# DM3370_IMU_BMI270.net
KiCad netlist of a schematic drawn in Altium Designer
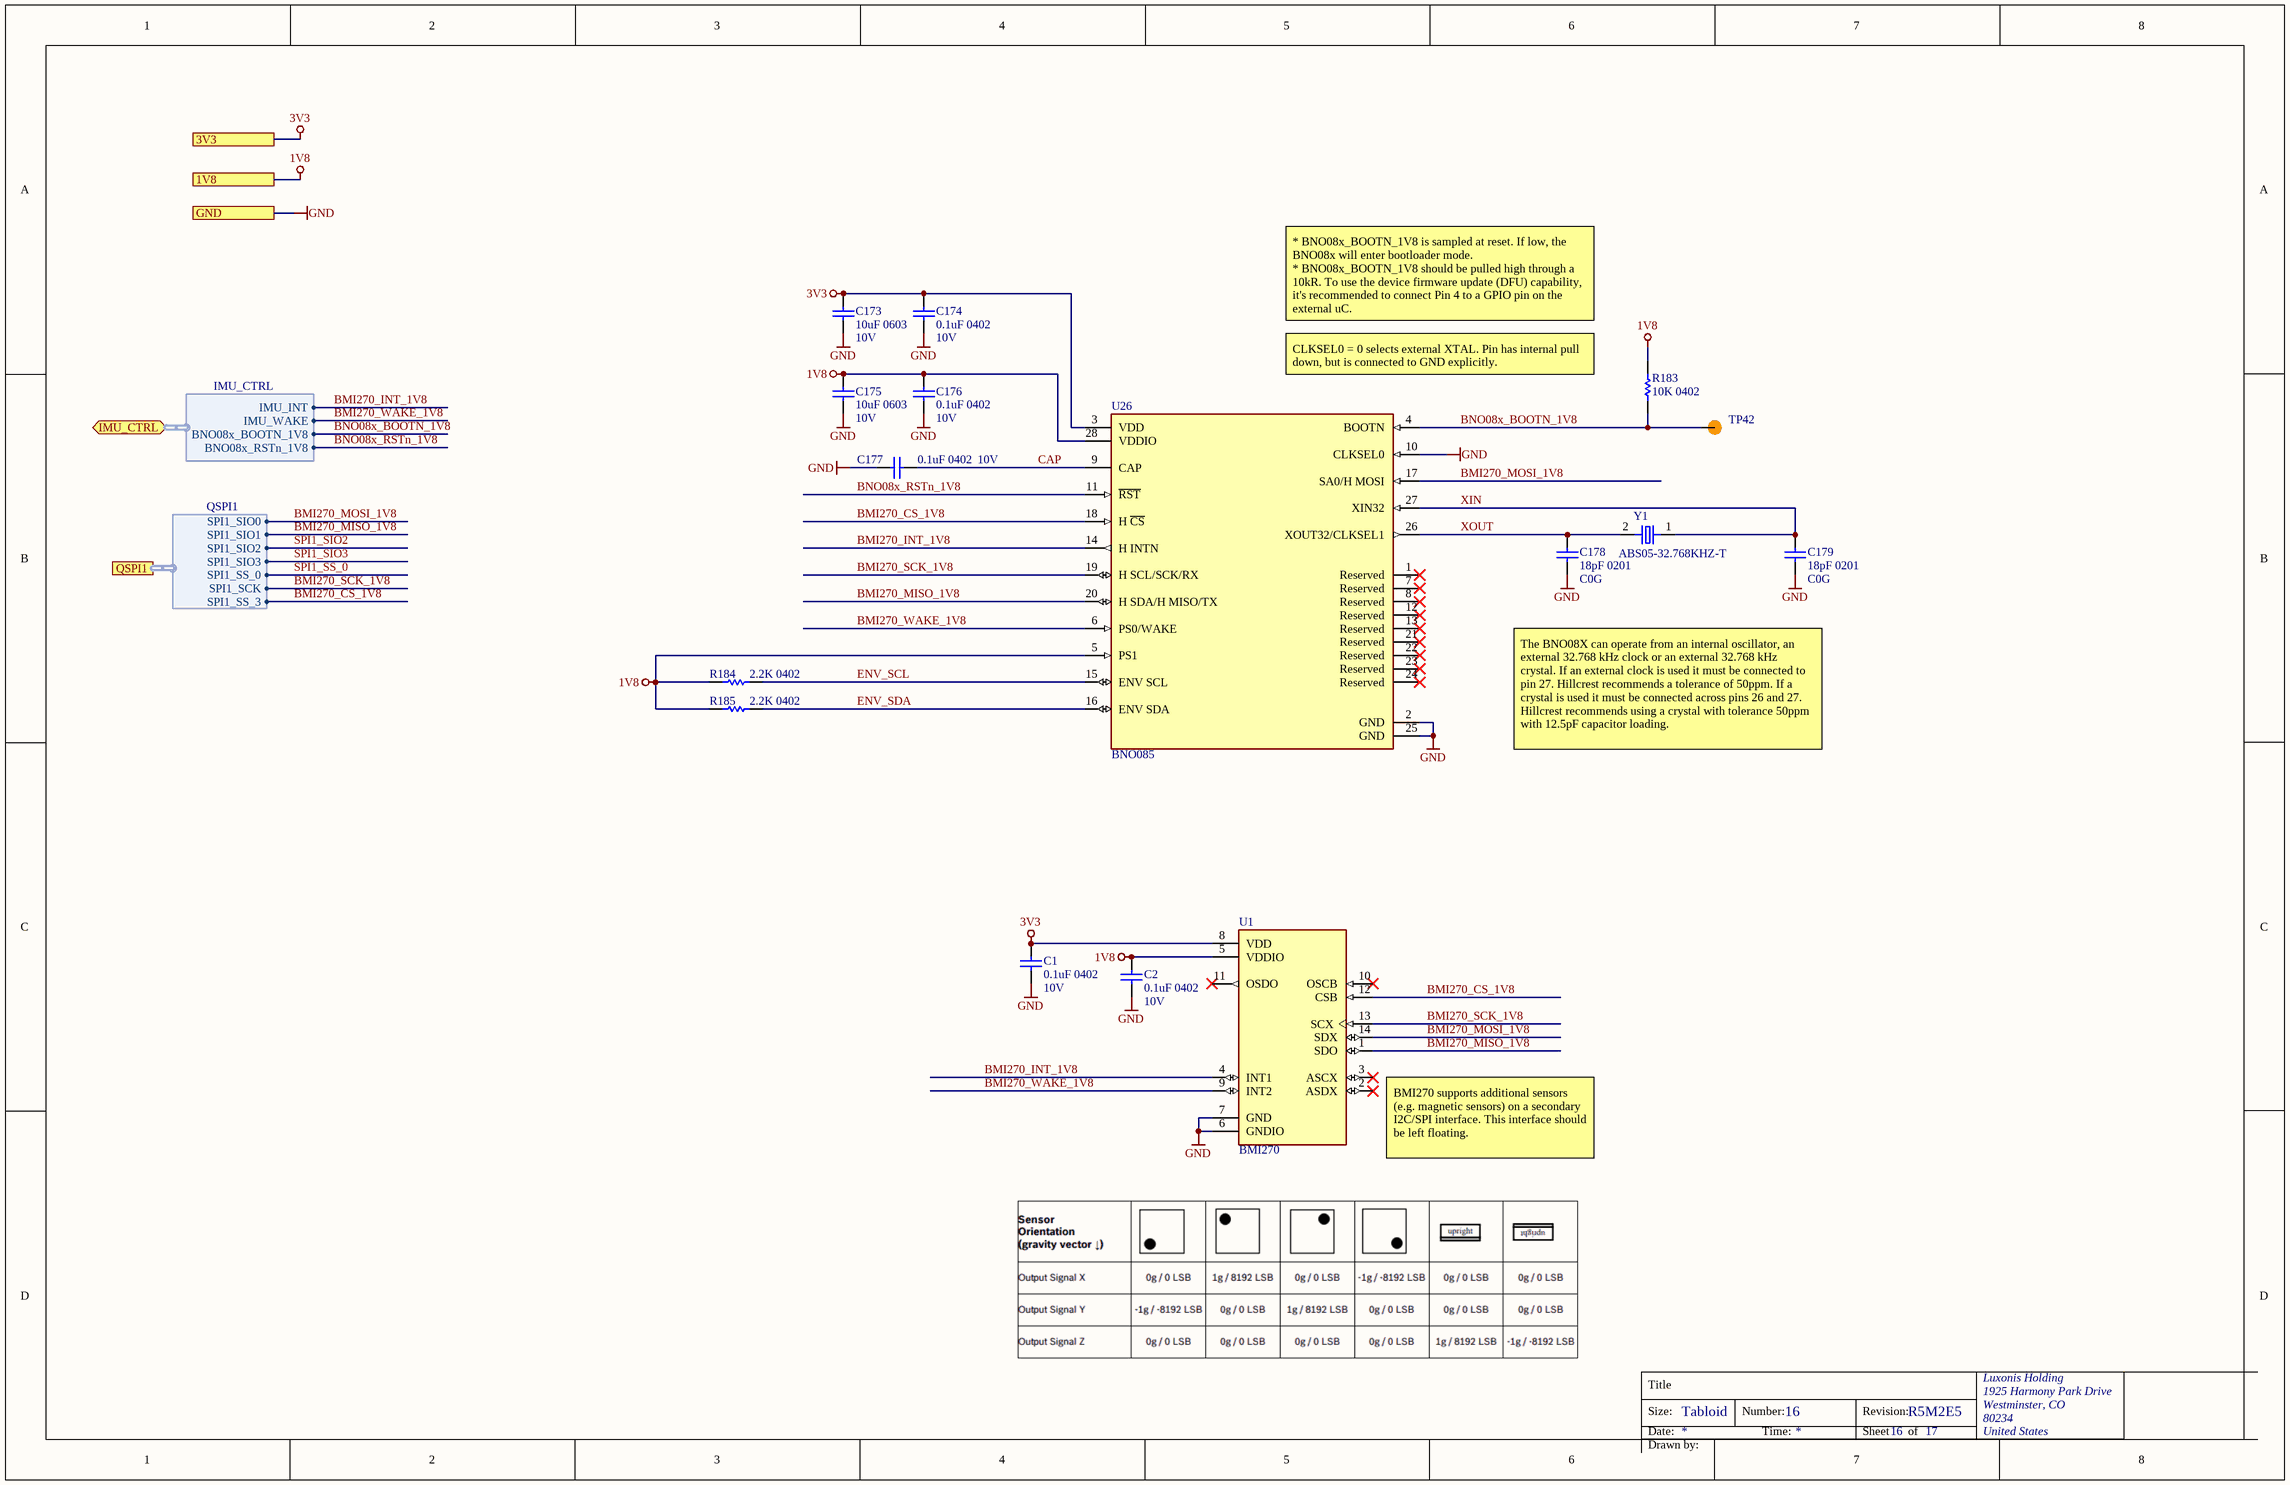
[diagram p0: DM3370_IMU_BMI270.SchDoc]

(export (version "E")
  (design (tool "Eeschema 10.0.6"))
  (components
    (comp (ref "C1")
      (value "0.1uF 0402")
      (footprint "CAP_Altium_Vault_Generic:CAPC0402(1005)70_L")
      (description "CAP CER 0.1UF 10V X7R 0402 5%")
      (fields (field (name "TOLERANCE") "5%") (field (name "VOLTAGE RATING") "10V"))
      (libsource (lib "LuxonisMaster") (part "GRM155R71A104JA01D"))
    )
    (comp (ref "C2")
      (value "0.1uF 0402")
      (footprint "CAP_Altium_Vault_Generic:CAPC0402(1005)70_L")
      (description "CAP CER 0.1UF 10V X7R 0402 5%")
      (fields (field (name "TOLERANCE") "5%") (field (name "VOLTAGE RATING") "10V"))
      (libsource (lib "LuxonisMaster") (part "GRM155R71A104JA01D"))
    )
    (comp (ref "C173")
      (value "10uF 0603")
      (footprint "CAP_Altium_Vault_Generic:CAPC0603(1608)100_L")
      (description "CAP CER 10UF 10V X5R 0603 20%")
      (fields (field (name "TOLERANCE") "20%") (field (name "VOLTAGE RATING") "10V"))
      (libsource (lib "LuxonisMaster") (part "GRM188R61A106ME69D"))
    )
    (comp (ref "C174")
      (value "0.1uF 0402")
      (footprint "CAP_Altium_Vault_Generic:CAPC0402(1005)70_L")
      (description "CAP CER 0.1UF 10V X7R 0402 5%")
      (fields (field (name "TOLERANCE") "5%") (field (name "VOLTAGE RATING") "10V"))
      (libsource (lib "LuxonisMaster") (part "GRM155R71A104JA01D"))
    )
    (comp (ref "C175")
      (value "10uF 0603")
      (footprint "CAP_Altium_Vault_Generic:CAPC0603(1608)100_L")
      (description "CAP CER 10UF 10V X5R 0603 20%")
      (fields (field (name "TOLERANCE") "20%") (field (name "VOLTAGE RATING") "10V"))
      (libsource (lib "LuxonisMaster") (part "GRM188R61A106ME69D"))
    )
    (comp (ref "C176")
      (value "0.1uF 0402")
      (footprint "CAP_Altium_Vault_Generic:CAPC0402(1005)70_L")
      (description "CAP CER 0.1UF 10V X7R 0402 5%")
      (fields (field (name "TOLERANCE") "5%") (field (name "VOLTAGE RATING") "10V"))
      (libsource (lib "LuxonisMaster") (part "GRM155R71A104JA01D"))
    )
    (comp (ref "C177")
      (value "0.1uF 0402")
      (footprint "CAP_Altium_Vault_Generic:CAPC0402(1005)70_L")
      (description "CAP CER 0.1UF 10V X7R 0402 5%")
      (fields (field (name "TOLERANCE") "5%") (field (name "VOLTAGE RATING") "10V"))
      (libsource (lib "LuxonisMaster") (part "GRM155R71A104JA01D"))
    )
    (comp (ref "C178")
      (value "18pF 0201")
      (footprint "CAPC0201(0603)33_L")
      (description "Cap Ceramic 18pF 25V C0G 1% Pad SMD 0201 125C T/R")
      (fields (field (name "TOLERANCE") "1%") (field (name "DIELECTRIC") "C0G"))
      (libsource (lib "LuxonisMaster") (part "GRM0335C1E180FA01D"))
    )
    (comp (ref "C179")
      (value "18pF 0201")
      (footprint "CAPC0201(0603)33_L")
      (description "Cap Ceramic 18pF 25V C0G 1% Pad SMD 0201 125C T/R")
      (fields (field (name "TOLERANCE") "1%") (field (name "DIELECTRIC") "C0G"))
      (libsource (lib "LuxonisMaster") (part "GRM0335C1E180FA01D"))
    )
    (comp (ref "R183")
      (value "10K 0402")
      (footprint "RES_Altium_Vault_Generic:RESC0402(1005)_L")
      (fields (field (name "TOLERANCE") "1%"))
      (libsource (lib "LuxonisMaster") (part "RC0402FR-1310KL"))
    )
    (comp (ref "R184")
      (value "2.2K 0402")
      (footprint "RES_Altium_Vault_Generic:RESC0402(1005)_L")
      (description "RES SMD 2.2K OHM 1% 1/16W 0402")
      (fields (field (name "TOLERANCE") "1%"))
      (libsource (lib "LuxonisMaster") (part "RC0402FR-072K2L"))
    )
    (comp (ref "R185")
      (value "2.2K 0402")
      (footprint "RES_Altium_Vault_Generic:RESC0402(1005)_L")
      (description "RES SMD 2.2K OHM 1% 1/16W 0402")
      (fields (field (name "TOLERANCE") "1%"))
      (libsource (lib "LuxonisMaster") (part "RC0402FR-072K2L"))
    )
    (comp (ref "TP42")
      (value "TP100_200_NS")
      (footprint "LuxonisMaster:TP100_200_NS")
      (libsource (lib "LuxonisMaster") (part "TEST_POINT"))
    )
    (comp (ref "U1")
      (value "BMI270")
      (footprint "XDCR_BMI270")
      (description "Accelerometer, Gyroscope, 6 Axis Sensor IÂ²C, SPI Output")
      (libsource (lib "LuxonisMaster") (part "BMI270"))
    )
    (comp (ref "U26")
      (value "BNO085")
      (footprint "BNO085")
      (description "IMU ACCEL/GYRO/MAG I2C 32BIT")
      (libsource (lib "LuxonisMaster") (part "BNO085"))
    )
    (comp (ref "Y1")
      (value "CMP-096-000000-2")
      (footprint "FP-ABS05-MFG")
      (description "CRYSTAL 32.7680KHZ 12.5PF SMD")
      (fields
        (field (name "TOLERANCE") "20ppm")
        (field (name "MANUFACTURER PART NUMBER 1") "ABS05-32.768KHZ-T")
      )
      (libsource (lib "Luxonis LLC") (part "ABS05-32.768KHZ-T"))
    )
  )
  (nets
    (net (code "3") (name "/BMI270_CS_1V8") (class "Default")
      (node (ref "U1") (pin "12") (pinfunction "CSB_12") (pintype "input"))
      (node (ref "U26") (pin "18") (pinfunction "H_~{CS}_18") (pintype "input"))
    )
    (net (code "4") (name "/BMI270_INT_1V8") (class "Default")
      (node (ref "U1") (pin "4") (pinfunction "INT1_4") (pintype "bidirectional"))
      (node (ref "U26") (pin "14") (pinfunction "H_INTN_14") (pintype "output"))
    )
    (net (code "5") (name "/BMI270_MISO_1V8") (class "Default")
      (node (ref "U1") (pin "1") (pinfunction "SDO_1") (pintype "bidirectional"))
      (node (ref "U26") (pin "20") (pinfunction "H_SDA/H_MISO/TX_20") (pintype "bidirectional"))
    )
    (net (code "6") (name "/BMI270_MOSI_1V8") (class "Default")
      (node (ref "U1") (pin "14") (pinfunction "SDX_14") (pintype "bidirectional"))
      (node (ref "U26") (pin "17") (pinfunction "SA0/H_MOSI_17") (pintype "input"))
    )
    (net (code "7") (name "/BMI270_SCK_1V8") (class "Default")
      (node (ref "U1") (pin "13") (pinfunction "SCX_13") (pintype "input"))
      (node (ref "U26") (pin "19") (pinfunction "H_SCL/SCK/RX_19") (pintype "bidirectional"))
    )
    (net (code "8") (name "/BMI270_WAKE_1V8") (class "Default")
      (node (ref "U1") (pin "9") (pinfunction "INT2_9") (pintype "bidirectional"))
      (node (ref "U26") (pin "6") (pinfunction "PS0/WAKE_6") (pintype "input"))
    )
    (net (code "9") (name "/BNO08x_BOOTN_1V8") (class "Default")
      (node (ref "R183") (pin "1") (pinfunction "1_1") (pintype "passive"))
      (node (ref "TP42") (pin "1") (pintype "passive"))
      (node (ref "U26") (pin "4") (pinfunction "BOOTN_4") (pintype "input"))
    )
    (net (code "10") (name "/BNO08x_RSTn_1V8") (class "Default")
      (node (ref "U26") (pin "11") (pinfunction "~{RST}_11") (pintype "input"))
    )
    (net (code "11") (name "/CAP") (class "Default")
      (node (ref "C177") (pin "1") (pinfunction "1_1") (pintype "passive"))
      (node (ref "U26") (pin "9") (pinfunction "CAP_9") (pintype "passive"))
    )
    (net (code "12") (name "/ENV_SCL") (class "Default")
      (node (ref "R184") (pin "2") (pinfunction "2_2") (pintype "passive"))
      (node (ref "U26") (pin "15") (pinfunction "ENV_SCL_15") (pintype "bidirectional"))
    )
    (net (code "13") (name "/ENV_SDA") (class "Default")
      (node (ref "R185") (pin "2") (pinfunction "2_2") (pintype "passive"))
      (node (ref "U26") (pin "16") (pinfunction "ENV_SDA_16") (pintype "bidirectional"))
    )
    (net (code "17") (name "/XIN") (class "Default")
      (node (ref "C179") (pin "2") (pinfunction "2_2") (pintype "passive"))
      (node (ref "U26") (pin "27") (pinfunction "XIN32_27") (pintype "input"))
      (node (ref "Y1") (pin "1") (pinfunction "1_1") (pintype "passive"))
    )
    (net (code "18") (name "/XOUT") (class "Default")
      (node (ref "C178") (pin "2") (pinfunction "2_2") (pintype "passive"))
      (node (ref "U26") (pin "26") (pinfunction "XOUT32/CLKSEL1_26") (pintype "output"))
      (node (ref "Y1") (pin "2") (pinfunction "2_2") (pintype "passive"))
    )
    (net (code "21") (name "1V8") (class "Default")
      (node (ref "C175") (pin "2") (pinfunction "2_2") (pintype "passive"))
      (node (ref "C176") (pin "2") (pinfunction "2_2") (pintype "passive"))
      (node (ref "C2") (pin "2") (pinfunction "2_2") (pintype "passive"))
      (node (ref "R183") (pin "2") (pinfunction "2_2") (pintype "passive"))
      (node (ref "R184") (pin "1") (pinfunction "1_1") (pintype "passive"))
      (node (ref "R185") (pin "1") (pinfunction "1_1") (pintype "passive"))
      (node (ref "U1") (pin "5") (pinfunction "VDDIO_5") (pintype "power_in"))
      (node (ref "U26") (pin "28") (pinfunction "VDDIO_28") (pintype "power_in"))
      (node (ref "U26") (pin "5") (pinfunction "PS1_5") (pintype "input"))
    )
    (net (code "22") (name "3V3") (class "Default")
      (node (ref "C1") (pin "2") (pinfunction "2_2") (pintype "passive"))
      (node (ref "C173") (pin "2") (pinfunction "2_2") (pintype "passive"))
      (node (ref "C174") (pin "2") (pinfunction "2_2") (pintype "passive"))
      (node (ref "U1") (pin "8") (pinfunction "VDD_8") (pintype "power_in"))
      (node (ref "U26") (pin "3") (pinfunction "VDD_3") (pintype "power_in"))
    )
    (net (code "23") (name "GND") (class "Default")
      (node (ref "C1") (pin "1") (pinfunction "1_1") (pintype "passive"))
      (node (ref "C173") (pin "1") (pinfunction "1_1") (pintype "passive"))
      (node (ref "C174") (pin "1") (pinfunction "1_1") (pintype "passive"))
      (node (ref "C175") (pin "1") (pinfunction "1_1") (pintype "passive"))
      (node (ref "C176") (pin "1") (pinfunction "1_1") (pintype "passive"))
      (node (ref "C177") (pin "2") (pinfunction "2_2") (pintype "passive"))
      (node (ref "C178") (pin "1") (pinfunction "1_1") (pintype "passive"))
      (node (ref "C179") (pin "1") (pinfunction "1_1") (pintype "passive"))
      (node (ref "C2") (pin "1") (pinfunction "1_1") (pintype "passive"))
      (node (ref "U1") (pin "6") (pinfunction "GNDIO_6") (pintype "power_in"))
      (node (ref "U1") (pin "7") (pinfunction "GND_7") (pintype "power_in"))
      (node (ref "U26") (pin "10") (pinfunction "CLKSEL0_10") (pintype "input"))
      (node (ref "U26") (pin "2") (pinfunction "GND_2") (pintype "power_in"))
      (node (ref "U26") (pin "25") (pinfunction "GND_25") (pintype "power_in"))
    )
    (net (code "24") (name "unconnected-(U1-ASCX-Pad3)") (class "Default")
      (node (ref "U1") (pin "3") (pinfunction "ASCX_3") (pintype "bidirectional+no_connect"))
    )
    (net (code "25") (name "unconnected-(U1-ASDX-Pad2)") (class "Default")
      (node (ref "U1") (pin "2") (pinfunction "ASDX_2") (pintype "bidirectional+no_connect"))
    )
    (net (code "26") (name "unconnected-(U1-OSCB-Pad10)") (class "Default")
      (node (ref "U1") (pin "10") (pinfunction "OSCB_10") (pintype "input+no_connect"))
    )
    (net (code "27") (name "unconnected-(U1-OSDO-Pad11)") (class "Default")
      (node (ref "U1") (pin "11") (pinfunction "OSDO_11") (pintype "output+no_connect"))
    )
    (net (code "28") (name "unconnected-(U26-Reserved-Pad1)") (class "Default")
      (node (ref "U26") (pin "1") (pinfunction "Reserved_1") (pintype "passive+no_connect"))
    )
    (net (code "29") (name "unconnected-(U26-Reserved-Pad7)") (class "Default")
      (node (ref "U26") (pin "7") (pinfunction "Reserved_7") (pintype "passive+no_connect"))
    )
    (net (code "30") (name "unconnected-(U26-Reserved-Pad8)") (class "Default")
      (node (ref "U26") (pin "8") (pinfunction "Reserved_8") (pintype "passive+no_connect"))
    )
    (net (code "31") (name "unconnected-(U26-Reserved-Pad12)") (class "Default")
      (node (ref "U26") (pin "12") (pinfunction "Reserved_12") (pintype "passive+no_connect"))
    )
    (net (code "32") (name "unconnected-(U26-Reserved-Pad13)") (class "Default")
      (node (ref "U26") (pin "13") (pinfunction "Reserved_13") (pintype "passive+no_connect"))
    )
    (net (code "33") (name "unconnected-(U26-Reserved-Pad21)") (class "Default")
      (node (ref "U26") (pin "21") (pinfunction "Reserved_21") (pintype "passive+no_connect"))
    )
    (net (code "34") (name "unconnected-(U26-Reserved-Pad22)") (class "Default")
      (node (ref "U26") (pin "22") (pinfunction "Reserved_22") (pintype "passive+no_connect"))
    )
    (net (code "35") (name "unconnected-(U26-Reserved-Pad23)") (class "Default")
      (node (ref "U26") (pin "23") (pinfunction "Reserved_23") (pintype "passive+no_connect"))
    )
    (net (code "36") (name "unconnected-(U26-Reserved-Pad24)") (class "Default")
      (node (ref "U26") (pin "24") (pinfunction "Reserved_24") (pintype "passive+no_connect"))
    )
  )
)
